# heat_bed_100.net
KiCad netlist of a schematic drawn in EAGLE
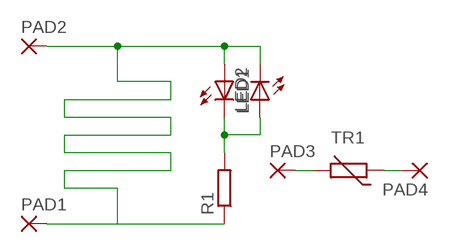
[diagram p0: schematic, sheet 1]

(export (version "E")
  (design (tool "Eeschema 10.0.6"))
  (components
    (comp (ref "LED1")
      (value "LEDSML0805")
      (footprint "eagle-import:SML0805")
      (libsource (lib "eagle-import") (part "LEDSML0805"))
    )
    (comp (ref "LED2")
      (value "LEDSML0805")
      (footprint "eagle-import:SML0805")
      (libsource (lib "eagle-import") (part "LEDSML0805"))
    )
    (comp (ref "PAD1")
      (value "2,54/1,0")
      (footprint "eagle-import:2,54_1,0")
      (libsource (lib "eagle-import") (part "2,54/1,0"))
    )
    (comp (ref "PAD2")
      (value "2,54/1,0")
      (footprint "eagle-import:2,54_1,0")
      (libsource (lib "eagle-import") (part "2,54/1,0"))
    )
    (comp (ref "PAD3")
      (value "2,54/1,0")
      (footprint "eagle-import:2,54_1,0")
      (libsource (lib "eagle-import") (part "2,54/1,0"))
    )
    (comp (ref "PAD4")
      (value "2,54/1,0")
      (footprint "eagle-import:2,54_1,0")
      (libsource (lib "eagle-import") (part "2,54/1,0"))
    )
    (comp (ref "R1")
      (value "R-EU_M1206")
      (footprint "eagle-import:M1206")
      (libsource (lib "eagle-import") (part "R-EU_M1206"))
    )
    (comp (ref "TR1")
      (value "THERMISTOR_R-5")
      (footprint "eagle-import:R-5")
      (libsource (lib "eagle-import") (part "THERMISTOR_R-5"))
    )
  )
  (nets
    (net (code "1") (name "Net-(LED1-PadC)") (class "Default")
      (node (ref "LED1") (pin "C") (pinfunction "C_C") (pintype "passive"))
      (node (ref "LED2") (pin "A") (pinfunction "A_A") (pintype "passive"))
      (node (ref "R1") (pin "2") (pinfunction "2_2") (pintype "passive"))
    )
    (net (code "2") (name "Net-(PAD1-P)") (class "Default")
      (node (ref "LED1") (pin "A") (pinfunction "A_A") (pintype "passive"))
      (node (ref "LED2") (pin "C") (pinfunction "C_C") (pintype "passive"))
      (node (ref "PAD1") (pin "1") (pinfunction "P_1") (pintype "passive"))
      (node (ref "PAD2") (pin "1") (pinfunction "P_1") (pintype "passive"))
      (node (ref "R1") (pin "1") (pinfunction "1_1") (pintype "passive"))
    )
    (net (code "3") (name "Net-(PAD3-P)") (class "Default")
      (node (ref "PAD3") (pin "1") (pinfunction "P_1") (pintype "passive"))
      (node (ref "TR1") (pin "2") (pinfunction "2_2") (pintype "passive"))
    )
    (net (code "4") (name "Net-(PAD4-P)") (class "Default")
      (node (ref "PAD4") (pin "1") (pinfunction "P_1") (pintype "passive"))
      (node (ref "TR1") (pin "1") (pinfunction "1_1") (pintype "passive"))
    )
  )
)
